# Buzzer.net
KiCad netlist of a schematic drawn in Altium Designer
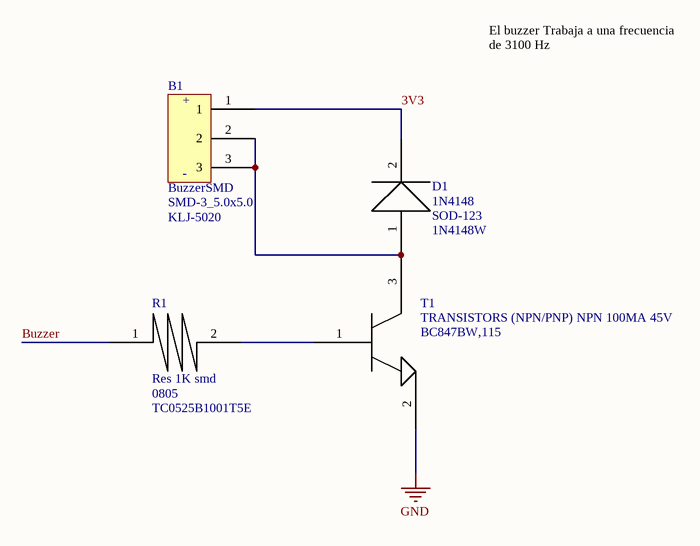
[diagram p0: Buzzer.SchDoc]

(export (version "E")
  (design (tool "Eeschema 10.0.6"))
  (components
    (comp (ref "B1")
      (value "BuzzerSMD")
      (footprint "BUZZERSMD")
      (fields (field (name "PACKAGE") "SMD-3_5.0x5.0") (field (name "MFR.PART #") "KLJ-5020"))
      (libsource (lib "Integrated_Library") (part "BuzzerSMD"))
    )
    (comp (ref "D1")
      (value "1N4148")
      (footprint "1N4148")
      (fields (field (name "PACKAGE") "SOD-123") (field (name "MFR.PART #") "1N4148W"))
      (libsource (lib "Integrated_Library") (part "1N4148"))
    )
    (comp (ref "R1")
      (value "Res 1K smd")
      (footprint "RES 1K")
      (fields (field (name "PACKAGE") "0805") (field (name "MFR.PART #") "TC0525B1001T5E"))
      (libsource (lib "Integrated_Library") (part "Res 1K smd"))
    )
    (comp (ref "T1")
      (value "TRANSISTORS (NPN/PNP) NPN 100MA 45V")
      (footprint "C8659")
      (description "TRANSISTORS (NPN/PNP) NPN 100MA 45V SOT-323(SC-70) ROHS")
      (fields (field (name "PACKAGE PART") "SOT-323-3") (field (name "SUPPLIER NUMBER PART") "BC847BW,115"))
      (libsource (lib "Practica 1") (part "C8659"))
    )
  )
  (nets
    (net (code "1") (name "/3V3") (class "Default")
      (node (ref "B1") (pin "1") (pinfunction "1_1") (pintype "passive"))
      (node (ref "D1") (pin "2") (pinfunction "2_2") (pintype "passive"))
    )
    (net (code "2") (name "/Buzzer") (class "Default")
      (node (ref "R1") (pin "1") (pinfunction "1_1") (pintype "passive"))
    )
    (net (code "3") (name "GND") (class "Default")
      (node (ref "T1") (pin "2") (pinfunction "2_2") (pintype "passive"))
    )
    (net (code "4") (name "Net-(B1-Pad2)") (class "Default")
      (node (ref "B1") (pin "2") (pinfunction "2_2") (pintype "passive"))
      (node (ref "B1") (pin "3") (pinfunction "3_3") (pintype "passive"))
      (node (ref "D1") (pin "1") (pinfunction "1_1") (pintype "passive"))
      (node (ref "T1") (pin "3") (pinfunction "3_3") (pintype "passive"))
    )
    (net (code "5") (name "Net-(R1-Pad2)") (class "Default")
      (node (ref "R1") (pin "2") (pinfunction "2_2") (pintype "passive"))
      (node (ref "T1") (pin "1") (pinfunction "1_1") (pintype "passive"))
    )
  )
)
